# SCH_DisenyPCB-Jordi_2025-02-20.net
KiCad netlist of a schematic drawn in EasyEDA
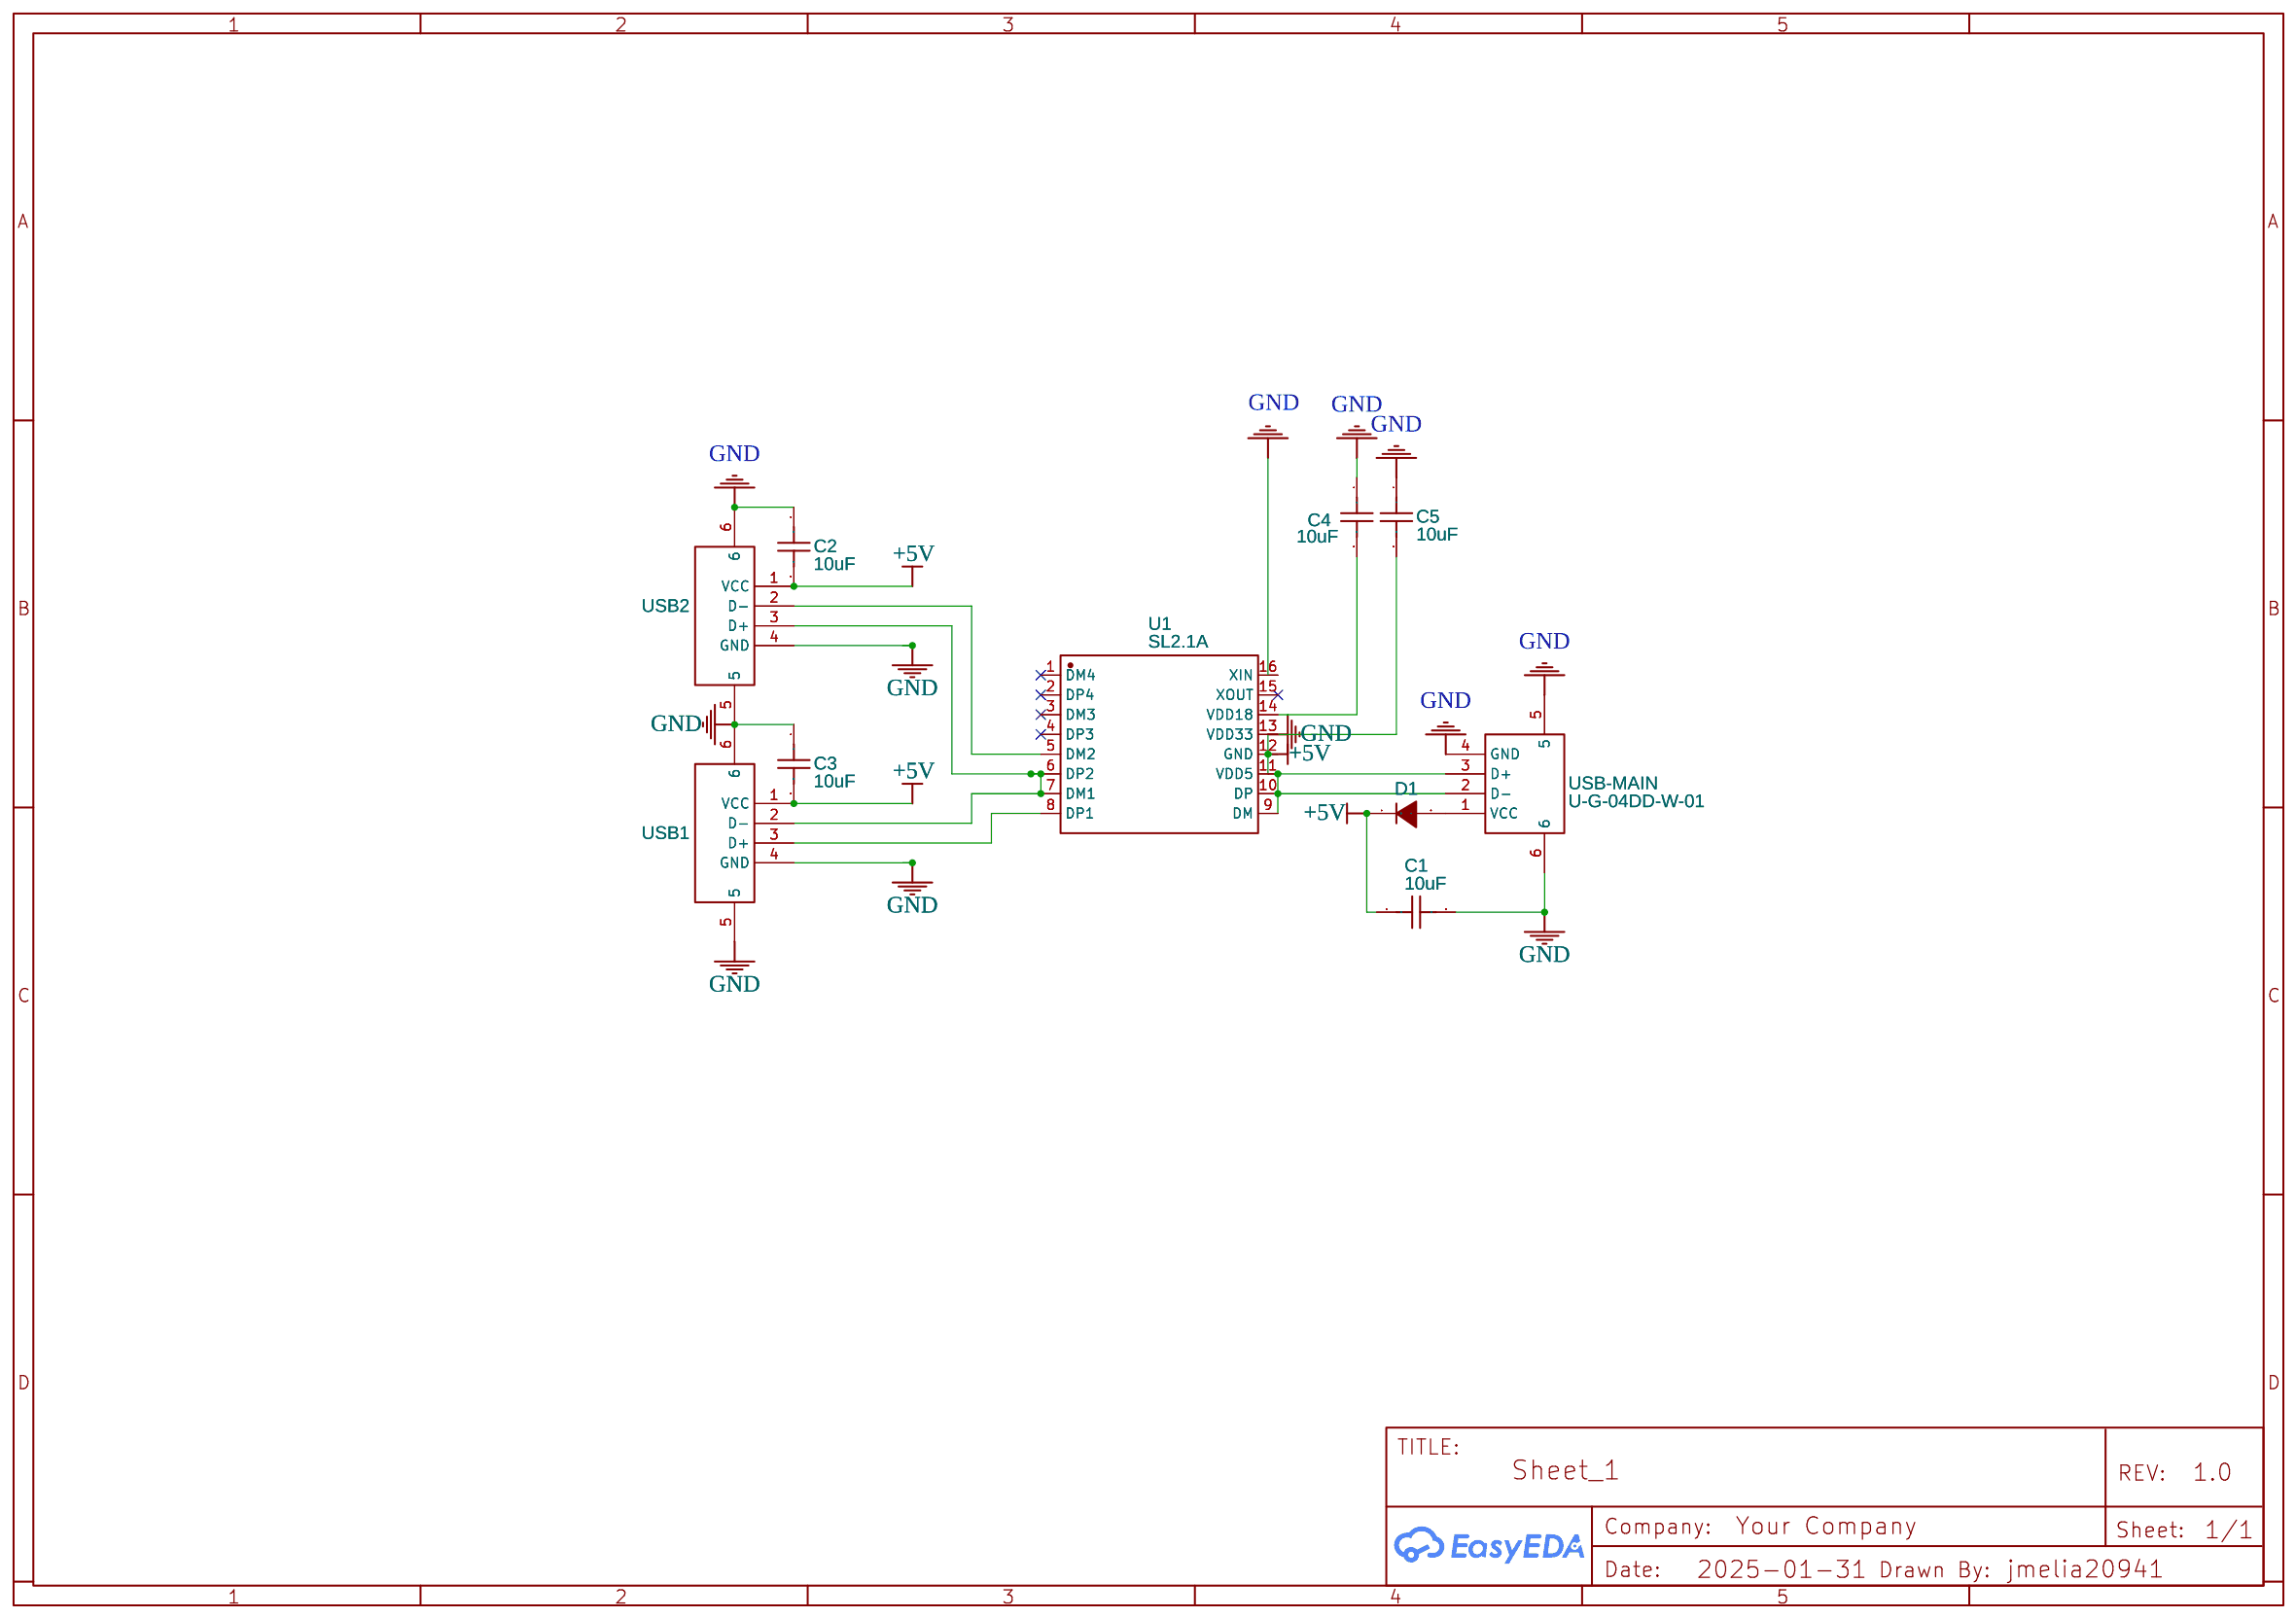
[diagram p0: schematic sheet]

(export (version "E")
  (design (tool "Eeschema 10.0.6"))
  (components
    (comp (ref "C1")
      (value "10uF")
      (fields
        (field (name "Manufacturer Part") "CL10A106KP8NNNC")
        (field (name "Manufacturer") "SAMSUNG(三星)")
      )
      (libsource (lib "") (part "CL10A106KP8NNNC_1"))
    )
    (comp (ref "C2")
      (value "10uF")
      (fields
        (field (name "Manufacturer Part") "CL10A106KP8NNNC")
        (field (name "Manufacturer") "SAMSUNG(三星)")
      )
      (libsource (lib "") (part "CL10A106KP8NNNC"))
    )
    (comp (ref "C3")
      (value "10uF")
      (fields
        (field (name "Manufacturer Part") "CL10A106KP8NNNC")
        (field (name "Manufacturer") "SAMSUNG(三星)")
      )
      (libsource (lib "") (part "CL10A106KP8NNNC"))
    )
    (comp (ref "C4")
      (value "10uF")
      (fields
        (field (name "Manufacturer Part") "CL10A106KP8NNNC")
        (field (name "Manufacturer") "SAMSUNG(三星)")
      )
      (libsource (lib "") (part "CL10A106KP8NNNC"))
    )
    (comp (ref "C5")
      (value "10uF")
      (fields
        (field (name "Manufacturer Part") "CL10A106KP8NNNC")
        (field (name "Manufacturer") "SAMSUNG(三星)")
      )
      (libsource (lib "") (part "CL10A106KP8NNNC"))
    )
    (comp (ref "D1")
      (value "D1")
      (fields (field (name "Manufacturer Part") "NSR0320MW2T1G") (field (name "Manufacturer") "onsemi(安森美)"))
      (libsource (lib "") (part "NSR0320MW2T1G"))
    )
    (comp (ref "U1")
      (value "SL2.1A")
      (fields (field (name "Manufacturer") "CoreChips(和芯润德)"))
      (libsource (lib "") (part "SL2.1A"))
    )
    (comp (ref "USB-MAIN")
      (value "U-G-04DD-W-01")
      (fields (field (name "Manufacturer Part") "U-G-O4DD-W-1") (field (name "Manufacturer") "韩国韩荣"))
      (libsource (lib "") (part "U-G-04DD-W-01"))
    )
    (comp (ref "USB1")
      (value "USB-AF-90-14.4X13.6-H7.0-DIP")
      (fields (field (name "Manufacturer Part") "903-131A1011D10100") (field (name "Manufacturer") "精拓金"))
      (libsource (lib "") (part "USB-AF-90-14.4X13.6-H7.0-DIP"))
    )
    (comp (ref "USB2")
      (value "USB-AF-90-14.4X13.6-H7.0-DIP")
      (fields (field (name "Manufacturer Part") "903-131A1011D10100") (field (name "Manufacturer") "精拓金"))
      (libsource (lib "") (part "USB-AF-90-14.4X13.6-H7.0-DIP"))
    )
  )
  (nets
    (net (code "1") (name "+5V") (class "Default")
      (node (ref "C1") (pin "1") (pinfunction "1_1") (pintype "unspecified"))
      (node (ref "C1") (pin "2") (pinfunction "2_2") (pintype "unspecified"))
      (node (ref "C2") (pin "1") (pinfunction "1_1") (pintype "unspecified"))
      (node (ref "C2") (pin "2") (pinfunction "2_2") (pintype "unspecified"))
      (node (ref "C3") (pin "1") (pinfunction "1_1") (pintype "unspecified"))
      (node (ref "C3") (pin "2") (pinfunction "2_2") (pintype "unspecified"))
      (node (ref "C4") (pin "1") (pinfunction "1_1") (pintype "unspecified"))
      (node (ref "C5") (pin "1") (pinfunction "1_1") (pintype "unspecified"))
      (node (ref "D1") (pin "1") (pinfunction "C_1") (pintype "unspecified"))
      (node (ref "U1") (pin "10") (pinfunction "DP_10") (pintype "unspecified"))
      (node (ref "U1") (pin "11") (pinfunction "VDD5_11") (pintype "unspecified"))
      (node (ref "U1") (pin "12") (pinfunction "GND_12") (pintype "unspecified"))
      (node (ref "U1") (pin "16") (pinfunction "XIN_16") (pintype "unspecified"))
      (node (ref "U1") (pin "9") (pinfunction "DM_9") (pintype "unspecified"))
      (node (ref "USB-MAIN") (pin "2") (pinfunction "D-_2") (pintype "unspecified"))
      (node (ref "USB-MAIN") (pin "3") (pinfunction "D+_3") (pintype "unspecified"))
      (node (ref "USB-MAIN") (pin "4") (pinfunction "GND_4") (pintype "unspecified"))
      (node (ref "USB-MAIN") (pin "5") (pinfunction "5_5") (pintype "unspecified"))
      (node (ref "USB-MAIN") (pin "6") (pinfunction "6_6") (pintype "unspecified"))
      (node (ref "USB1") (pin "1") (pinfunction "VCC_1") (pintype "unspecified"))
      (node (ref "USB1") (pin "4") (pinfunction "GND_4") (pintype "unspecified"))
      (node (ref "USB1") (pin "5") (pinfunction "5_5") (pintype "unspecified"))
      (node (ref "USB1") (pin "6") (pinfunction "6_6") (pintype "unspecified"))
      (node (ref "USB2") (pin "1") (pinfunction "VCC_1") (pintype "unspecified"))
      (node (ref "USB2") (pin "4") (pinfunction "GND_4") (pintype "unspecified"))
      (node (ref "USB2") (pin "5") (pinfunction "5_5") (pintype "unspecified"))
      (node (ref "USB2") (pin "6") (pinfunction "6_6") (pintype "unspecified"))
    )
    (net (code "2") (name "Net-(D1-A)") (class "Default")
      (node (ref "D1") (pin "2") (pinfunction "A_2") (pintype "unspecified"))
      (node (ref "USB-MAIN") (pin "1") (pinfunction "VCC_1") (pintype "unspecified"))
    )
    (net (code "3") (name "Net-(U1-DM1)") (class "Default")
      (node (ref "U1") (pin "6") (pinfunction "DP2_6") (pintype "unspecified"))
      (node (ref "U1") (pin "7") (pinfunction "DM1_7") (pintype "unspecified"))
      (node (ref "USB1") (pin "2") (pinfunction "D-_2") (pintype "unspecified"))
      (node (ref "USB2") (pin "3") (pinfunction "D+_3") (pintype "unspecified"))
    )
    (net (code "4") (name "Net-(U1-DM2)") (class "Default")
      (node (ref "U1") (pin "5") (pinfunction "DM2_5") (pintype "unspecified"))
      (node (ref "USB2") (pin "2") (pinfunction "D-_2") (pintype "unspecified"))
    )
    (net (code "5") (name "Net-(U1-DP1)") (class "Default")
      (node (ref "U1") (pin "8") (pinfunction "DP1_8") (pintype "unspecified"))
      (node (ref "USB1") (pin "3") (pinfunction "D+_3") (pintype "unspecified"))
    )
    (net (code "6") (name "Net-(U1-VDD18)") (class "Default")
      (node (ref "C4") (pin "2") (pinfunction "2_2") (pintype "unspecified"))
      (node (ref "U1") (pin "14") (pinfunction "VDD18_14") (pintype "unspecified"))
    )
    (net (code "7") (name "Net-(U1-VDD33)") (class "Default")
      (node (ref "C5") (pin "2") (pinfunction "2_2") (pintype "unspecified"))
      (node (ref "U1") (pin "13") (pinfunction "VDD33_13") (pintype "unspecified"))
    )
    (net (code "8") (name "unconnected-(U1-DM3-Pad3)") (class "Default")
      (node (ref "U1") (pin "3") (pinfunction "DM3_3") (pintype "unspecified+no_connect"))
    )
    (net (code "9") (name "unconnected-(U1-DM4-Pad1)") (class "Default")
      (node (ref "U1") (pin "1") (pinfunction "DM4_1") (pintype "unspecified+no_connect"))
    )
    (net (code "10") (name "unconnected-(U1-DP3-Pad4)") (class "Default")
      (node (ref "U1") (pin "4") (pinfunction "DP3_4") (pintype "unspecified+no_connect"))
    )
    (net (code "11") (name "unconnected-(U1-DP4-Pad2)") (class "Default")
      (node (ref "U1") (pin "2") (pinfunction "DP4_2") (pintype "unspecified+no_connect"))
    )
    (net (code "12") (name "unconnected-(U1-XOUT-Pad15)") (class "Default")
      (node (ref "U1") (pin "15") (pinfunction "XOUT_15") (pintype "unspecified+no_connect"))
    )
  )
)
